# jogwheel.net
KiCad netlist of a schematic drawn in EAGLE
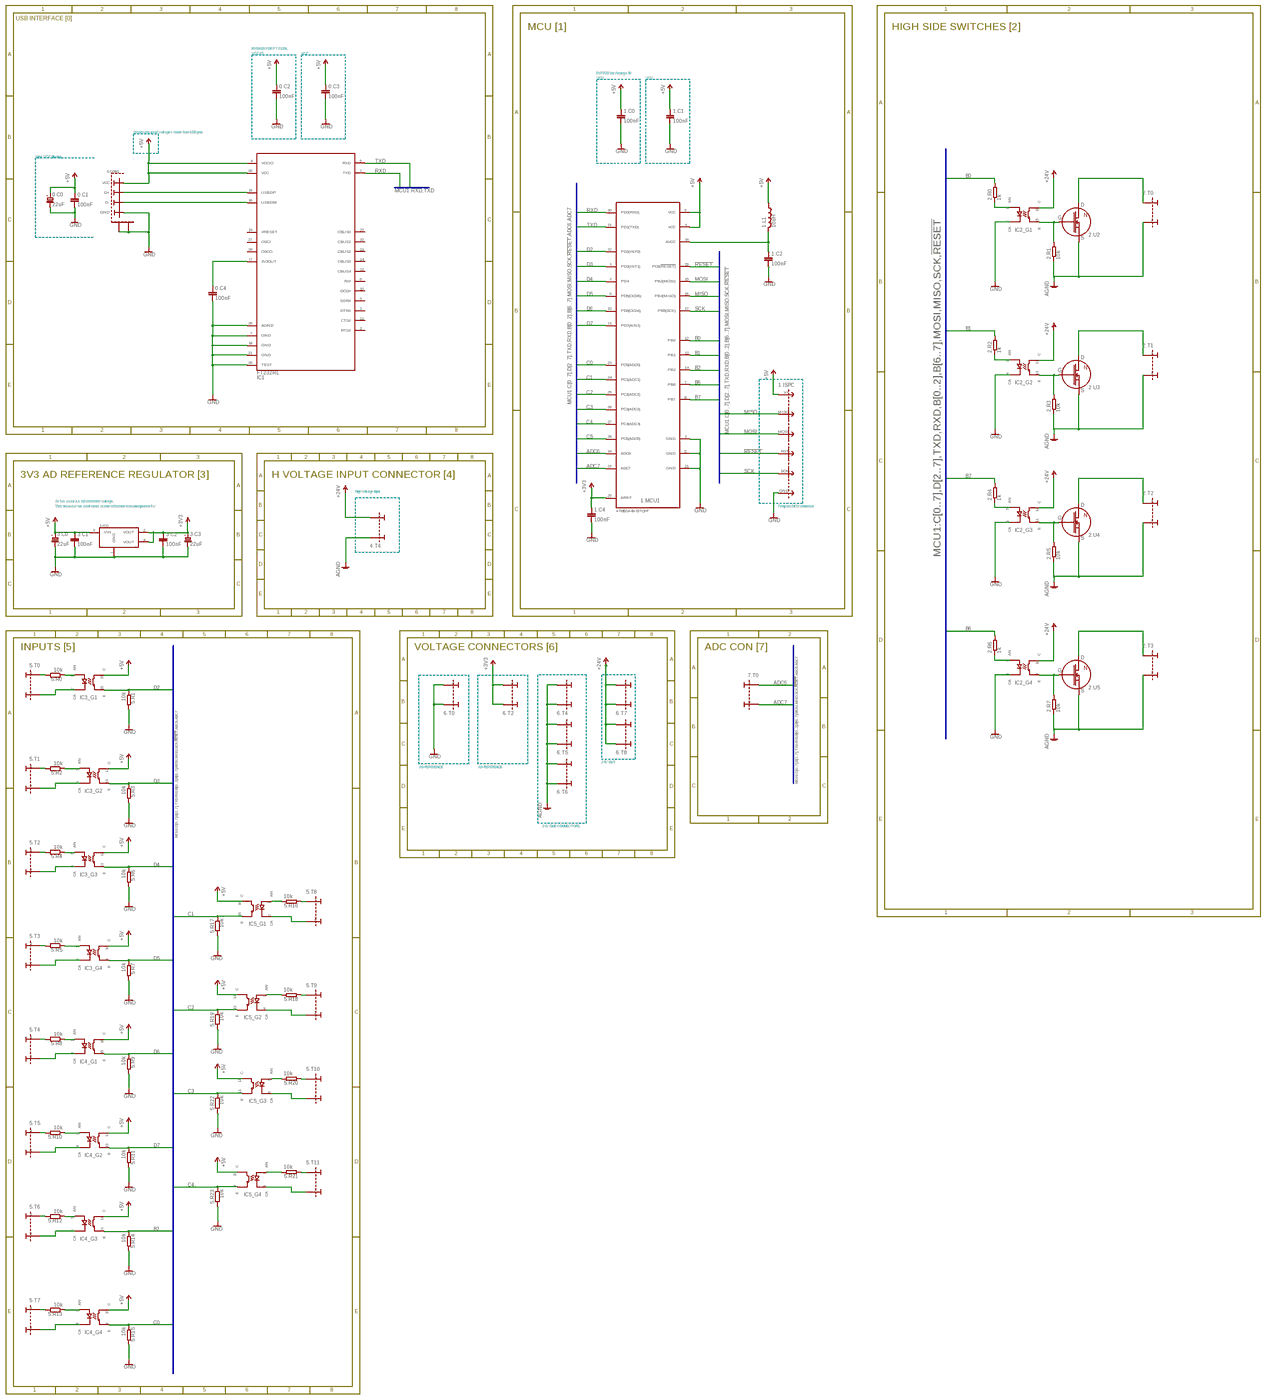
[diagram p0: schematic, sheet 1, overview]
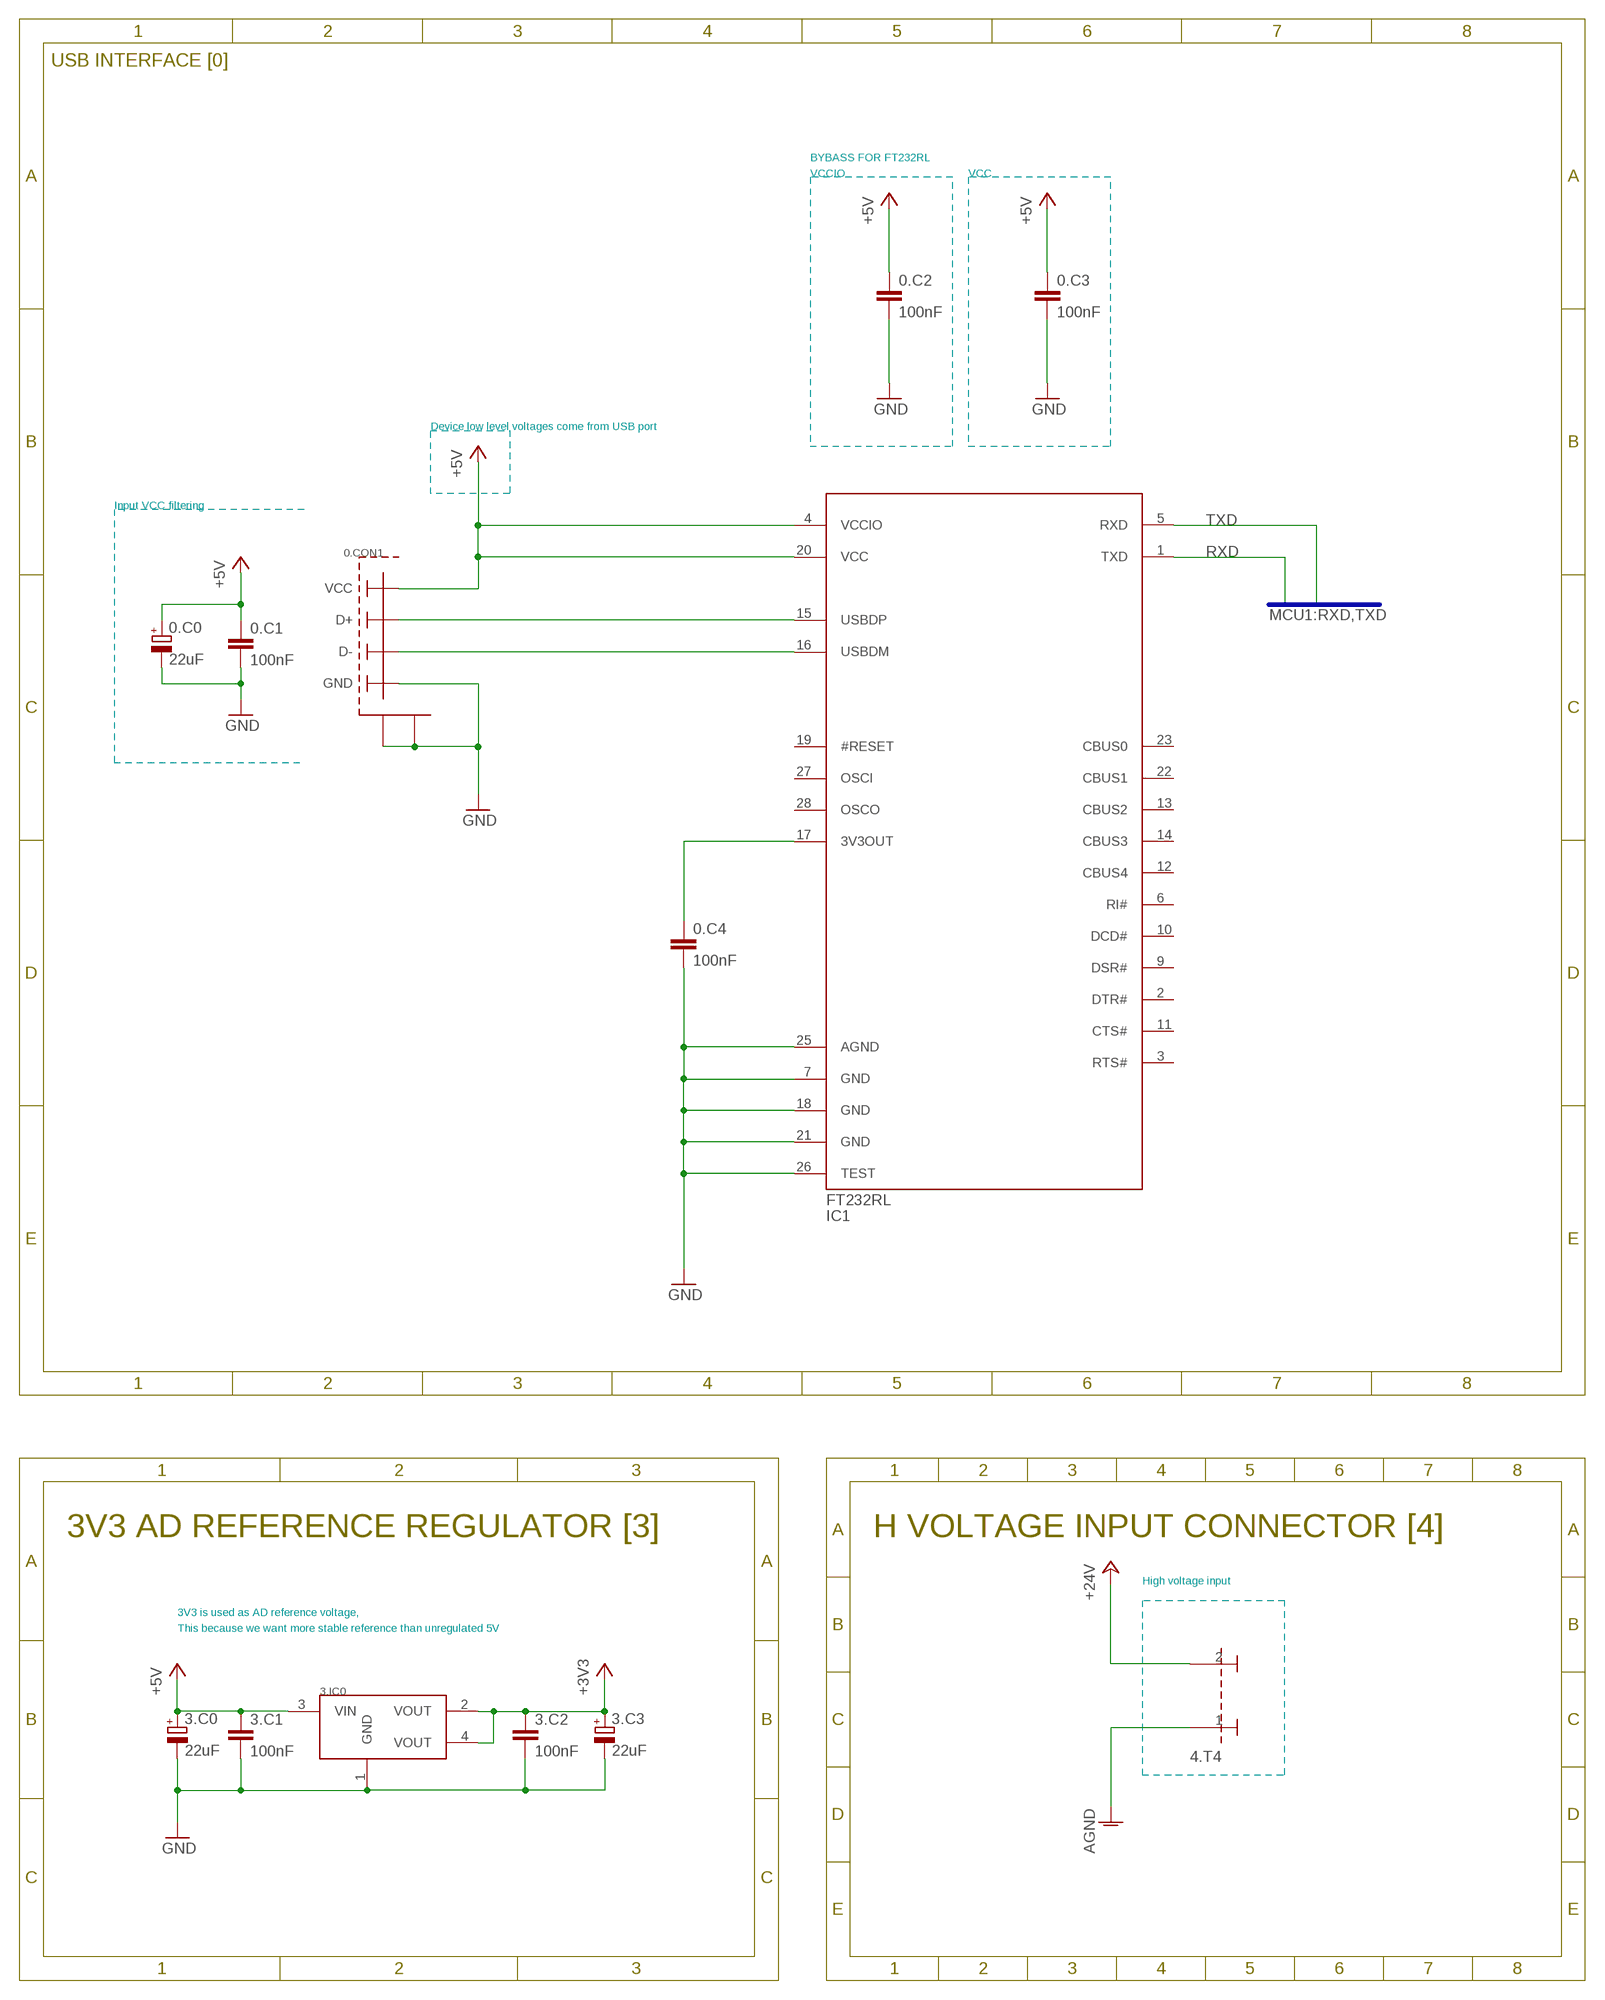
[diagram p1: schematic, sheet 1, part 1 of 4]
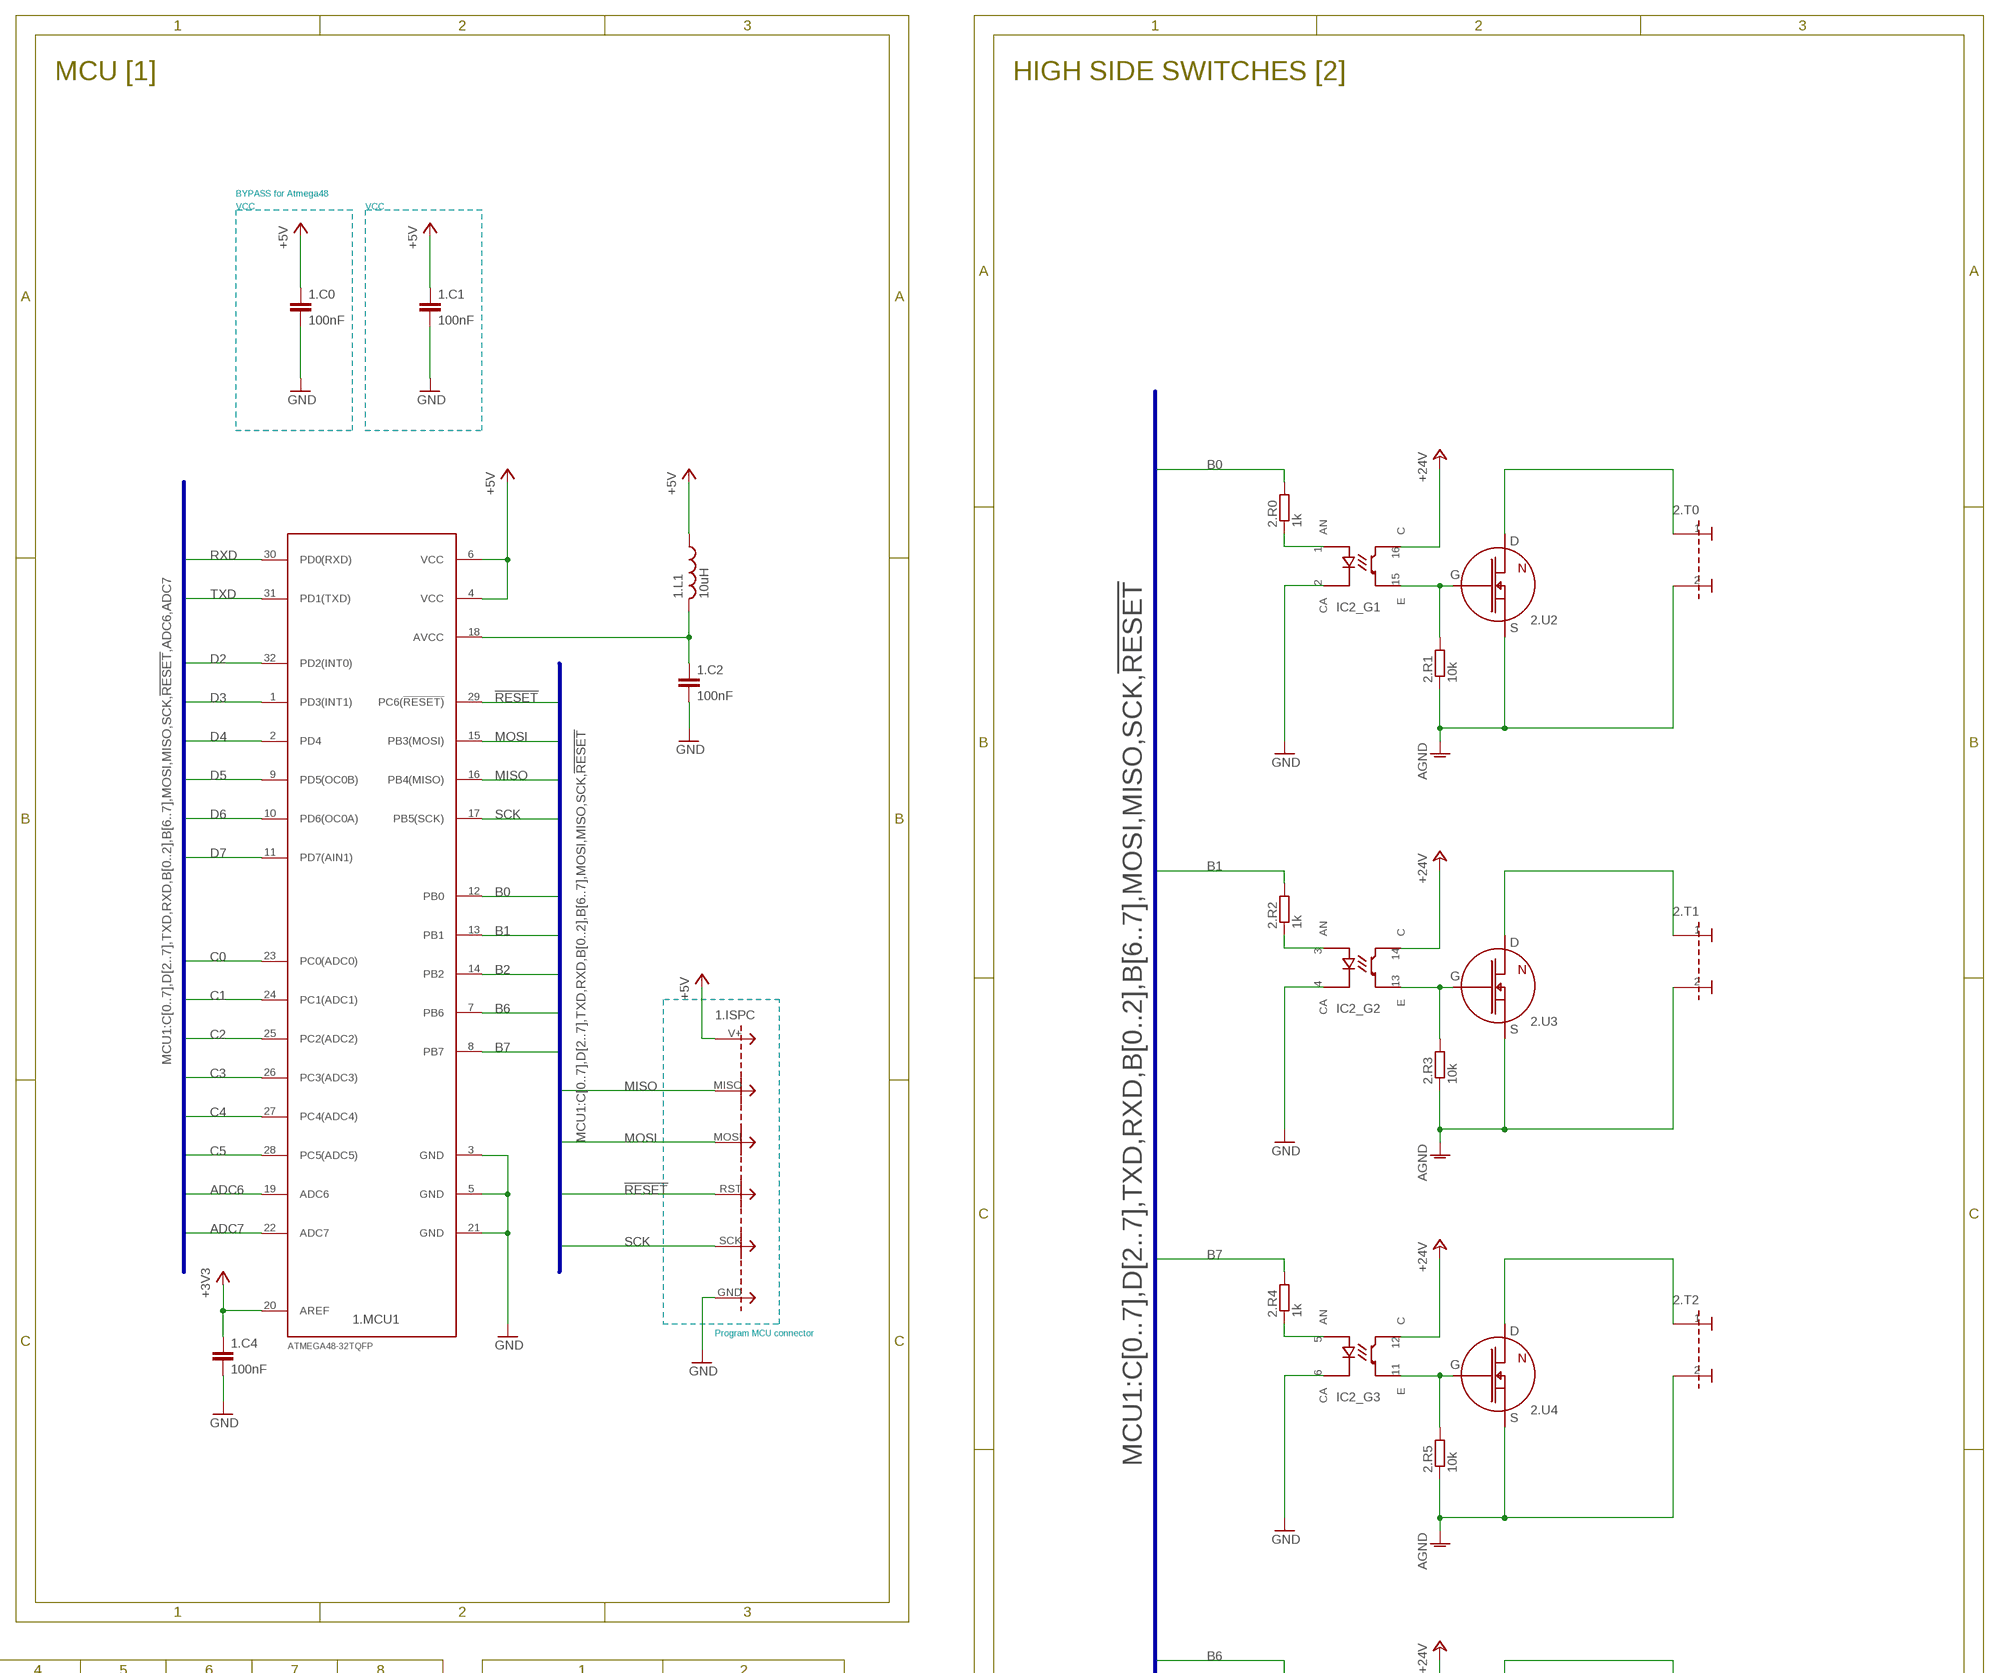
[diagram p2: schematic, sheet 1, part 2 of 4]
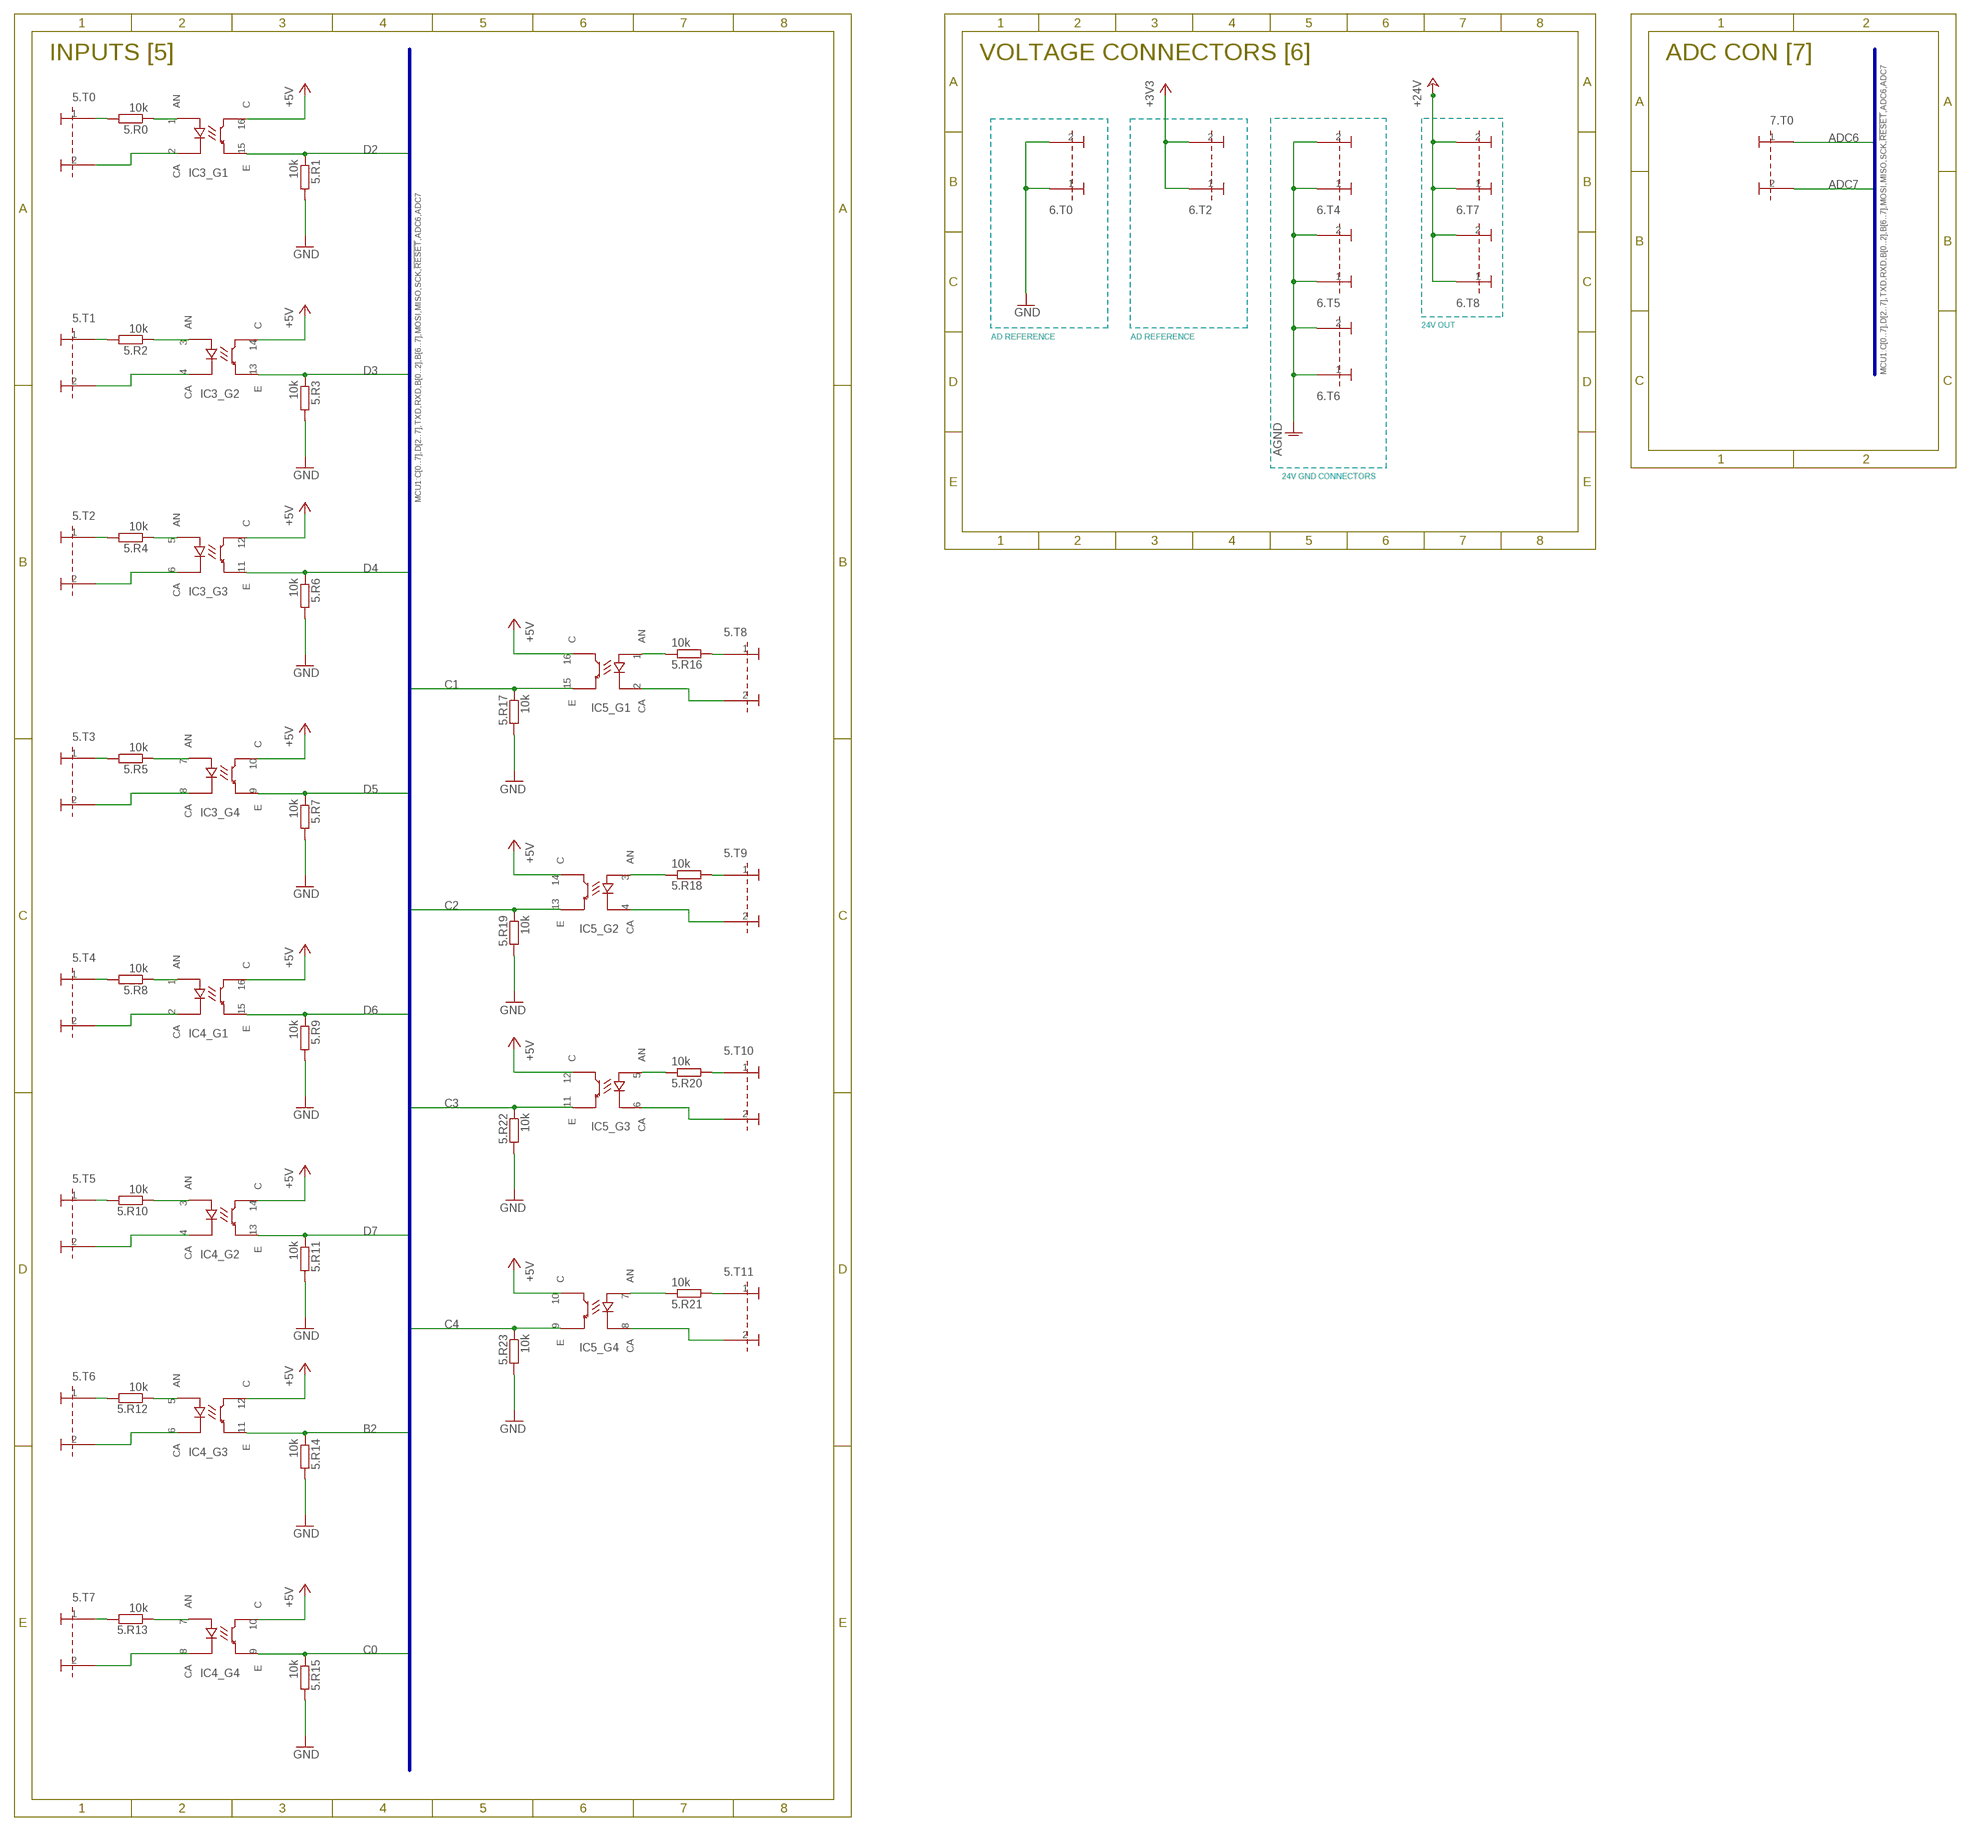
[diagram p3: schematic, sheet 1, part 3 of 4]
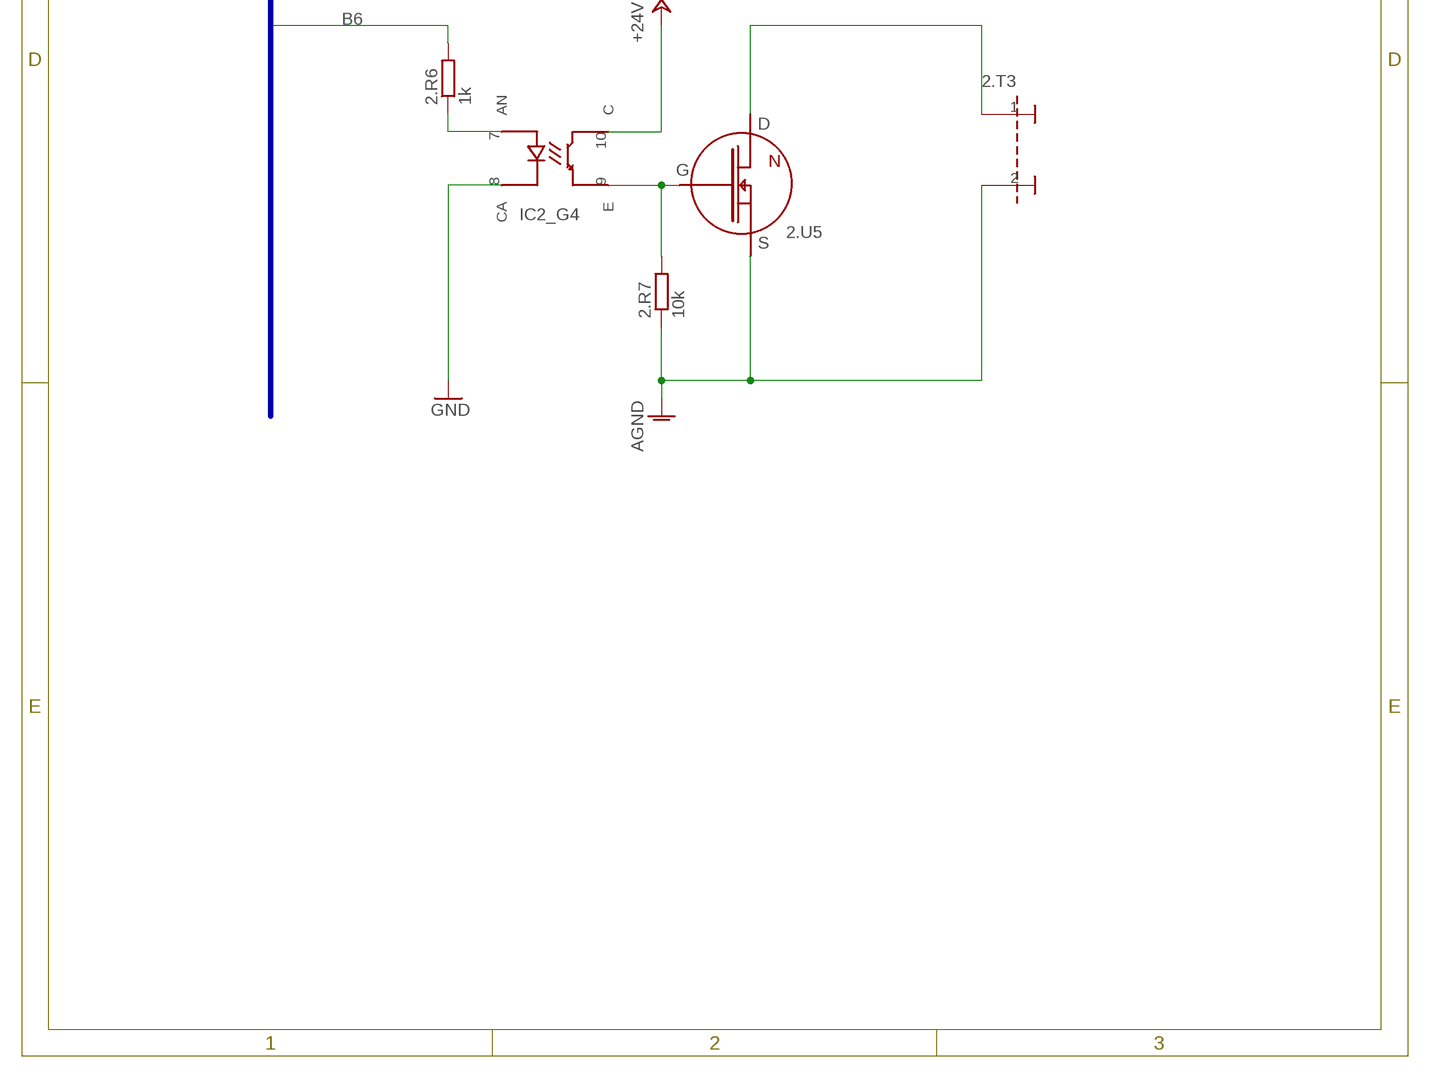
[diagram p4: schematic, sheet 1, part 4 of 4]

(export (version "E")
  (design (tool "Eeschema 10.0.6"))
  (components
    (comp (ref "0.C0")
      (value "22uF")
      (footprint "eagle-import:E1.5-5")
      (libsource (lib "eagle-import") (part "CPOL-EUE1.5-5"))
    )
    (comp (ref "0.C1")
      (value "100nF")
      (footprint "eagle-import:C0805")
      (libsource (lib "eagle-import") (part "C-EUC0805"))
    )
    (comp (ref "0.C2")
      (value "100nF")
      (footprint "eagle-import:C0805")
      (libsource (lib "eagle-import") (part "C-EUC0805"))
    )
    (comp (ref "0.C3")
      (value "100nF")
      (footprint "eagle-import:C0805")
      (libsource (lib "eagle-import") (part "C-EUC0805"))
    )
    (comp (ref "0.C4")
      (value "100nF")
      (footprint "eagle-import:C0805")
      (libsource (lib "eagle-import") (part "C-EUC0805"))
    )
    (comp (ref "0.CON1")
      (value "USB-BWUERTH-ELECTRONIC-USB-B")
      (footprint "eagle-import:USB-B-THROUGH-HOLE")
      (libsource (lib "eagle-import") (part "USB-BWUERTH-ELECTRONIC-USB-B"))
    )
    (comp (ref "1.C0")
      (value "100nF")
      (footprint "eagle-import:C0805")
      (libsource (lib "eagle-import") (part "C-EUC0805"))
    )
    (comp (ref "1.C1")
      (value "100nF")
      (footprint "eagle-import:C0805")
      (libsource (lib "eagle-import") (part "C-EUC0805"))
    )
    (comp (ref "1.C2")
      (value "100nF")
      (footprint "eagle-import:C0805")
      (libsource (lib "eagle-import") (part "C-EUC0805"))
    )
    (comp (ref "1.C4")
      (value "100nF")
      (footprint "eagle-import:C0805")
      (libsource (lib "eagle-import") (part "C-EUC0805"))
    )
    (comp (ref "1.ISPC")
      (value "CONNECTOR_6PIN2X3_ISP")
      (footprint "eagle-import:2X3_ISP")
      (libsource (lib "eagle-import") (part "CONNECTOR_6PIN2X3_ISP"))
    )
    (comp (ref "1.L1")
      (value "10uH")
      (footprint "eagle-import:C0805")
      (libsource (lib "eagle-import") (part "L_10UH_0805_LB2012T100KR"))
    )
    (comp (ref "1.MCU1")
      (value "ATMEGA48-20PU-32TQFPTQFP32")
      (footprint "eagle-import:TQFP32-08")
      (libsource (lib "eagle-import") (part "ATMEGA48-20PU-32TQFPTQFP32"))
    )
    (comp (ref "2.R0")
      (value "1k")
      (footprint "eagle-import:R0805")
      (libsource (lib "eagle-import") (part "R-EU_R0805"))
    )
    (comp (ref "2.R1")
      (value "10k")
      (footprint "eagle-import:R0805")
      (libsource (lib "eagle-import") (part "R-EU_R0805"))
    )
    (comp (ref "2.R2")
      (value "1k")
      (footprint "eagle-import:R0805")
      (libsource (lib "eagle-import") (part "R-EU_R0805"))
    )
    (comp (ref "2.R3")
      (value "10k")
      (footprint "eagle-import:R0805")
      (libsource (lib "eagle-import") (part "R-EU_R0805"))
    )
    (comp (ref "2.R4")
      (value "1k")
      (footprint "eagle-import:R0805")
      (libsource (lib "eagle-import") (part "R-EU_R0805"))
    )
    (comp (ref "2.R5")
      (value "10k")
      (footprint "eagle-import:R0805")
      (libsource (lib "eagle-import") (part "R-EU_R0805"))
    )
    (comp (ref "2.R6")
      (value "1k")
      (footprint "eagle-import:R0805")
      (libsource (lib "eagle-import") (part "R-EU_R0805"))
    )
    (comp (ref "2.R7")
      (value "10k")
      (footprint "eagle-import:R0805")
      (libsource (lib "eagle-import") (part "R-EU_R0805"))
    )
    (comp (ref "2.T0")
      (value "CONNECTOR_2PIN2W-TERMINAL-HEADER-20.155MV/2")
      (footprint "eagle-import:2WAY-TERMINAL-HEADER-20.155MV_2")
      (fields (field (name "PIN1") "DRAIN") (field (name "PIN2") "AGND"))
      (libsource (lib "eagle-import") (part "CONNECTOR_2PIN2W-TERMINAL-HEADER-20.155MV/2"))
    )
    (comp (ref "2.T1")
      (value "CONNECTOR_2PIN2W-TERMINAL-HEADER-20.155MV/2")
      (footprint "eagle-import:2WAY-TERMINAL-HEADER-20.155MV_2")
      (fields (field (name "PIN1") "DRAIN") (field (name "PIN2") "AGND"))
      (libsource (lib "eagle-import") (part "CONNECTOR_2PIN2W-TERMINAL-HEADER-20.155MV/2"))
    )
    (comp (ref "2.T2")
      (value "CONNECTOR_2PIN2W-TERMINAL-HEADER-20.155MV/2")
      (footprint "eagle-import:2WAY-TERMINAL-HEADER-20.155MV_2")
      (fields (field (name "PIN1") "DRAIN") (field (name "PIN2") "AGND"))
      (libsource (lib "eagle-import") (part "CONNECTOR_2PIN2W-TERMINAL-HEADER-20.155MV/2"))
    )
    (comp (ref "2.T3")
      (value "CONNECTOR_2PIN2W-TERMINAL-HEADER-20.155MV/2")
      (footprint "eagle-import:2WAY-TERMINAL-HEADER-20.155MV_2")
      (fields (field (name "PIN1") "DRAIN") (field (name "PIN2") "AGND"))
      (libsource (lib "eagle-import") (part "CONNECTOR_2PIN2W-TERMINAL-HEADER-20.155MV/2"))
    )
    (comp (ref "2.U2")
      (value "N_MOSFET_STD6NF10")
      (footprint "eagle-import:STD6NF10")
      (libsource (lib "eagle-import") (part "N_MOSFET_STD6NF10"))
    )
    (comp (ref "2.U3")
      (value "N_MOSFET_STD6NF10")
      (footprint "eagle-import:STD6NF10")
      (libsource (lib "eagle-import") (part "N_MOSFET_STD6NF10"))
    )
    (comp (ref "2.U4")
      (value "N_MOSFET_STD6NF10")
      (footprint "eagle-import:STD6NF10")
      (libsource (lib "eagle-import") (part "N_MOSFET_STD6NF10"))
    )
    (comp (ref "2.U5")
      (value "N_MOSFET_STD6NF10")
      (footprint "eagle-import:STD6NF10")
      (libsource (lib "eagle-import") (part "N_MOSFET_STD6NF10"))
    )
    (comp (ref "3.C0")
      (value "22uF")
      (footprint "eagle-import:E1.5-5")
      (libsource (lib "eagle-import") (part "CPOL-EUE1.5-5"))
    )
    (comp (ref "3.C1")
      (value "100nF")
      (footprint "eagle-import:C0805")
      (libsource (lib "eagle-import") (part "C-EUC0805"))
    )
    (comp (ref "3.C2")
      (value "100nF")
      (footprint "eagle-import:C0805")
      (libsource (lib "eagle-import") (part "C-EUC0805"))
    )
    (comp (ref "3.C3")
      (value "22uF")
      (footprint "eagle-import:E1.5-5")
      (libsource (lib "eagle-import") (part "CPOL-EUE1.5-5"))
    )
    (comp (ref "3.IC0")
      (value "REGULATOR_AP1117E33G-13")
      (footprint "eagle-import:SOT223")
      (libsource (lib "eagle-import") (part "REGULATOR_AP1117E33G-13"))
    )
    (comp (ref "4.T4")
      (value "CONNECTOR_2PIN2W-TERMINAL-HEADER-20.155MV/2")
      (footprint "eagle-import:2WAY-TERMINAL-HEADER-20.155MV_2")
      (fields (field (name "PIN1") "AGND") (field (name "PIN2") "24VIN"))
      (libsource (lib "eagle-import") (part "CONNECTOR_2PIN2W-TERMINAL-HEADER-20.155MV/2"))
    )
    (comp (ref "5.R0")
      (value "10k")
      (footprint "eagle-import:R0805")
      (libsource (lib "eagle-import") (part "R-EU_R0805"))
    )
    (comp (ref "5.R1")
      (value "10k")
      (footprint "eagle-import:R0805")
      (libsource (lib "eagle-import") (part "R-EU_R0805"))
    )
    (comp (ref "5.R2")
      (value "10k")
      (footprint "eagle-import:R0805")
      (libsource (lib "eagle-import") (part "R-EU_R0805"))
    )
    (comp (ref "5.R3")
      (value "10k")
      (footprint "eagle-import:R0805")
      (libsource (lib "eagle-import") (part "R-EU_R0805"))
    )
    (comp (ref "5.R4")
      (value "10k")
      (footprint "eagle-import:R0805")
      (libsource (lib "eagle-import") (part "R-EU_R0805"))
    )
    (comp (ref "5.R5")
      (value "10k")
      (footprint "eagle-import:R0805")
      (libsource (lib "eagle-import") (part "R-EU_R0805"))
    )
    (comp (ref "5.R6")
      (value "10k")
      (footprint "eagle-import:R0805")
      (libsource (lib "eagle-import") (part "R-EU_R0805"))
    )
    (comp (ref "5.R7")
      (value "10k")
      (footprint "eagle-import:R0805")
      (libsource (lib "eagle-import") (part "R-EU_R0805"))
    )
    (comp (ref "5.R8")
      (value "10k")
      (footprint "eagle-import:R0805")
      (libsource (lib "eagle-import") (part "R-EU_R0805"))
    )
    (comp (ref "5.R9")
      (value "10k")
      (footprint "eagle-import:R0805")
      (libsource (lib "eagle-import") (part "R-EU_R0805"))
    )
    (comp (ref "5.R10")
      (value "10k")
      (footprint "eagle-import:R0805")
      (libsource (lib "eagle-import") (part "R-EU_R0805"))
    )
    (comp (ref "5.R11")
      (value "10k")
      (footprint "eagle-import:R0805")
      (libsource (lib "eagle-import") (part "R-EU_R0805"))
    )
    (comp (ref "5.R12")
      (value "10k")
      (footprint "eagle-import:R0805")
      (libsource (lib "eagle-import") (part "R-EU_R0805"))
    )
    (comp (ref "5.R13")
      (value "10k")
      (footprint "eagle-import:R0805")
      (libsource (lib "eagle-import") (part "R-EU_R0805"))
    )
    (comp (ref "5.R14")
      (value "10k")
      (footprint "eagle-import:R0805")
      (libsource (lib "eagle-import") (part "R-EU_R0805"))
    )
    (comp (ref "5.R15")
      (value "10k")
      (footprint "eagle-import:R0805")
      (libsource (lib "eagle-import") (part "R-EU_R0805"))
    )
    (comp (ref "5.R16")
      (value "10k")
      (footprint "eagle-import:R0805")
      (libsource (lib "eagle-import") (part "R-EU_R0805"))
    )
    (comp (ref "5.R17")
      (value "10k")
      (footprint "eagle-import:R0805")
      (libsource (lib "eagle-import") (part "R-EU_R0805"))
    )
    (comp (ref "5.R18")
      (value "10k")
      (footprint "eagle-import:R0805")
      (libsource (lib "eagle-import") (part "R-EU_R0805"))
    )
    (comp (ref "5.R19")
      (value "10k")
      (footprint "eagle-import:R0805")
      (libsource (lib "eagle-import") (part "R-EU_R0805"))
    )
    (comp (ref "5.R20")
      (value "10k")
      (footprint "eagle-import:R0805")
      (libsource (lib "eagle-import") (part "R-EU_R0805"))
    )
    (comp (ref "5.R21")
      (value "10k")
      (footprint "eagle-import:R0805")
      (libsource (lib "eagle-import") (part "R-EU_R0805"))
    )
    (comp (ref "5.R22")
      (value "10k")
      (footprint "eagle-import:R0805")
      (libsource (lib "eagle-import") (part "R-EU_R0805"))
    )
    (comp (ref "5.R23")
      (value "10k")
      (footprint "eagle-import:R0805")
      (libsource (lib "eagle-import") (part "R-EU_R0805"))
    )
    (comp (ref "5.T0")
      (value "CONNECTOR_2PIN2W-TERMINAL-HEADER-20.155MV/2")
      (footprint "eagle-import:2WAY-TERMINAL-HEADER-20.155MV_2")
      (fields (field (name "PIN1") "V+") (field (name "PIN2") "V-"))
      (libsource (lib "eagle-import") (part "CONNECTOR_2PIN2W-TERMINAL-HEADER-20.155MV/2"))
    )
    (comp (ref "5.T1")
      (value "CONNECTOR_2PIN2W-TERMINAL-HEADER-20.155MV/2")
      (footprint "eagle-import:2WAY-TERMINAL-HEADER-20.155MV_2")
      (fields (field (name "PIN1") "V+") (field (name "PIN2") "V-"))
      (libsource (lib "eagle-import") (part "CONNECTOR_2PIN2W-TERMINAL-HEADER-20.155MV/2"))
    )
    (comp (ref "5.T2")
      (value "CONNECTOR_2PIN2W-TERMINAL-HEADER-20.155MV/2")
      (footprint "eagle-import:2WAY-TERMINAL-HEADER-20.155MV_2")
      (fields (field (name "PIN1") "V+") (field (name "PIN2") "V-"))
      (libsource (lib "eagle-import") (part "CONNECTOR_2PIN2W-TERMINAL-HEADER-20.155MV/2"))
    )
    (comp (ref "5.T3")
      (value "CONNECTOR_2PIN2W-TERMINAL-HEADER-20.155MV/2")
      (footprint "eagle-import:2WAY-TERMINAL-HEADER-20.155MV_2")
      (fields (field (name "PIN1") "V+") (field (name "PIN2") "V-"))
      (libsource (lib "eagle-import") (part "CONNECTOR_2PIN2W-TERMINAL-HEADER-20.155MV/2"))
    )
    (comp (ref "5.T4")
      (value "CONNECTOR_2PIN2W-TERMINAL-HEADER-20.155MV/2")
      (footprint "eagle-import:2WAY-TERMINAL-HEADER-20.155MV_2")
      (fields (field (name "PIN1") "V+") (field (name "PIN2") "V-"))
      (libsource (lib "eagle-import") (part "CONNECTOR_2PIN2W-TERMINAL-HEADER-20.155MV/2"))
    )
    (comp (ref "5.T5")
      (value "CONNECTOR_2PIN2W-TERMINAL-HEADER-20.155MV/2")
      (footprint "eagle-import:2WAY-TERMINAL-HEADER-20.155MV_2")
      (fields (field (name "PIN1") "V+") (field (name "PIN2") "V-"))
      (libsource (lib "eagle-import") (part "CONNECTOR_2PIN2W-TERMINAL-HEADER-20.155MV/2"))
    )
    (comp (ref "5.T6")
      (value "CONNECTOR_2PIN2W-TERMINAL-HEADER-20.155MV/2")
      (footprint "eagle-import:2WAY-TERMINAL-HEADER-20.155MV_2")
      (fields (field (name "PIN1") "V+") (field (name "PIN2") "V-"))
      (libsource (lib "eagle-import") (part "CONNECTOR_2PIN2W-TERMINAL-HEADER-20.155MV/2"))
    )
    (comp (ref "5.T7")
      (value "CONNECTOR_2PIN2W-TERMINAL-HEADER-20.155MV/2")
      (footprint "eagle-import:2WAY-TERMINAL-HEADER-20.155MV_2")
      (fields (field (name "PIN1") "V+") (field (name "PIN2") "V-"))
      (libsource (lib "eagle-import") (part "CONNECTOR_2PIN2W-TERMINAL-HEADER-20.155MV/2"))
    )
    (comp (ref "5.T8")
      (value "CONNECTOR_2PIN2W-TERMINAL-HEADER-20.155MV/2")
      (footprint "eagle-import:2WAY-TERMINAL-HEADER-20.155MV_2")
      (fields (field (name "PIN1") "V+") (field (name "PIN2") "V-"))
      (libsource (lib "eagle-import") (part "CONNECTOR_2PIN2W-TERMINAL-HEADER-20.155MV/2"))
    )
    (comp (ref "5.T9")
      (value "CONNECTOR_2PIN2W-TERMINAL-HEADER-20.155MV/2")
      (footprint "eagle-import:2WAY-TERMINAL-HEADER-20.155MV_2")
      (fields (field (name "PIN1") "V+") (field (name "PIN2") "V-"))
      (libsource (lib "eagle-import") (part "CONNECTOR_2PIN2W-TERMINAL-HEADER-20.155MV/2"))
    )
    (comp (ref "5.T10")
      (value "CONNECTOR_2PIN2W-TERMINAL-HEADER-20.155MV/2")
      (footprint "eagle-import:2WAY-TERMINAL-HEADER-20.155MV_2")
      (fields (field (name "PIN1") "V+") (field (name "PIN2") "V-"))
      (libsource (lib "eagle-import") (part "CONNECTOR_2PIN2W-TERMINAL-HEADER-20.155MV/2"))
    )
    (comp (ref "5.T11")
      (value "CONNECTOR_2PIN2W-TERMINAL-HEADER-20.155MV/2")
      (footprint "eagle-import:2WAY-TERMINAL-HEADER-20.155MV_2")
      (fields (field (name "PIN1") "V+") (field (name "PIN2") "V-"))
      (libsource (lib "eagle-import") (part "CONNECTOR_2PIN2W-TERMINAL-HEADER-20.155MV/2"))
    )
    (comp (ref "6.T0")
      (value "CONNECTOR_2PIN2W-TERMINAL-HEADER-20.155MV/2")
      (footprint "eagle-import:2WAY-TERMINAL-HEADER-20.155MV_2")
      (fields (field (name "PIN1") "GND") (field (name "PIN2") "GND"))
      (libsource (lib "eagle-import") (part "CONNECTOR_2PIN2W-TERMINAL-HEADER-20.155MV/2"))
    )
    (comp (ref "6.T2")
      (value "CONNECTOR_2PIN2W-TERMINAL-HEADER-20.155MV/2")
      (footprint "eagle-import:2WAY-TERMINAL-HEADER-20.155MV_2")
      (fields (field (name "PIN1") "AREF") (field (name "PIN2") "AREF"))
      (libsource (lib "eagle-import") (part "CONNECTOR_2PIN2W-TERMINAL-HEADER-20.155MV/2"))
    )
    (comp (ref "6.T4")
      (value "CONNECTOR_2PIN2W-TERMINAL-HEADER-20.155MV/2")
      (footprint "eagle-import:2WAY-TERMINAL-HEADER-20.155MV_2")
      (fields (field (name "PIN1") "AGND") (field (name "PIN2") "AGND"))
      (libsource (lib "eagle-import") (part "CONNECTOR_2PIN2W-TERMINAL-HEADER-20.155MV/2"))
    )
    (comp (ref "6.T5")
      (value "CONNECTOR_2PIN2W-TERMINAL-HEADER-20.155MV/2")
      (footprint "eagle-import:2WAY-TERMINAL-HEADER-20.155MV_2")
      (fields (field (name "PIN1") "AGND") (field (name "PIN2") "AGND"))
      (libsource (lib "eagle-import") (part "CONNECTOR_2PIN2W-TERMINAL-HEADER-20.155MV/2"))
    )
    (comp (ref "6.T6")
      (value "CONNECTOR_2PIN2W-TERMINAL-HEADER-20.155MV/2")
      (footprint "eagle-import:2WAY-TERMINAL-HEADER-20.155MV_2")
      (fields (field (name "PIN1") "AGND") (field (name "PIN2") "AGND"))
      (libsource (lib "eagle-import") (part "CONNECTOR_2PIN2W-TERMINAL-HEADER-20.155MV/2"))
    )
    (comp (ref "6.T7")
      (value "CONNECTOR_2PIN2W-TERMINAL-HEADER-20.155MV/2")
      (footprint "eagle-import:2WAY-TERMINAL-HEADER-20.155MV_2")
      (fields (field (name "PIN1") "24V") (field (name "PIN2") "24V"))
      (libsource (lib "eagle-import") (part "CONNECTOR_2PIN2W-TERMINAL-HEADER-20.155MV/2"))
    )
    (comp (ref "6.T8")
      (value "CONNECTOR_2PIN2W-TERMINAL-HEADER-20.155MV/2")
      (footprint "eagle-import:2WAY-TERMINAL-HEADER-20.155MV_2")
      (fields (field (name "PIN1") "24V") (field (name "PIN2") "24V"))
      (libsource (lib "eagle-import") (part "CONNECTOR_2PIN2W-TERMINAL-HEADER-20.155MV/2"))
    )
    (comp (ref "7.T0")
      (value "CONNECTOR_2PIN2W-TERMINAL-HEADER-20.155MV/2")
      (footprint "eagle-import:2WAY-TERMINAL-HEADER-20.155MV_2")
      (fields (field (name "PIN1") "ADC0") (field (name "PIN2") "ADC1"))
      (libsource (lib "eagle-import") (part "CONNECTOR_2PIN2W-TERMINAL-HEADER-20.155MV/2"))
    )
    (comp (ref "IC1")
      (value "FT232RL")
      (footprint "eagle-import:SSOP28")
      (libsource (lib "eagle-import") (part "FT232RL"))
    )
    (comp (ref "IC2")
      (value "OPTO_4_CHANNELS")
      (footprint "eagle-import:ACPL-845-O300")
      (libsource (lib "eagle-import") (part "OPTO_4_CHANNELS"))
    )
    (comp (ref "IC3")
      (value "OPTO_4_CHANNELS")
      (footprint "eagle-import:ACPL-845-O300")
      (libsource (lib "eagle-import") (part "OPTO_4_CHANNELS"))
    )
    (comp (ref "IC4")
      (value "OPTO_4_CHANNELS")
      (footprint "eagle-import:ACPL-845-O300")
      (libsource (lib "eagle-import") (part "OPTO_4_CHANNELS"))
    )
    (comp (ref "IC5")
      (value "OPTO_4_CHANNELS")
      (footprint "eagle-import:ACPL-845-O300")
      (libsource (lib "eagle-import") (part "OPTO_4_CHANNELS"))
    )
  )
  (nets
    (net (code "2") (name "+3V3") (class "Default")
      (node (ref "1.C4") (pin "1") (pinfunction "1_1") (pintype "passive"))
      (node (ref "1.MCU1") (pin "20") (pinfunction "AREF_20") (pintype "bidirectional"))
      (node (ref "3.C2") (pin "1") (pinfunction "1_1") (pintype "passive"))
      (node (ref "3.C3") (pin "+") (pinfunction "+_+") (pintype "passive"))
      (node (ref "3.IC0") (pin "2") (pinfunction "VOUT_2") (pintype "bidirectional"))
      (node (ref "3.IC0") (pin "4") (pinfunction "VOUT_4") (pintype "bidirectional"))
      (node (ref "6.T2") (pin "1") (pinfunction "P$1_1") (pintype "bidirectional"))
      (node (ref "6.T2") (pin "2") (pinfunction "P$2_2") (pintype "bidirectional"))
    )
    (net (code "3") (name "+5V") (class "Default")
      (node (ref "0.C0") (pin "+") (pinfunction "+_+") (pintype "passive"))
      (node (ref "0.C1") (pin "1") (pinfunction "1_1") (pintype "passive"))
      (node (ref "0.C2") (pin "1") (pinfunction "1_1") (pintype "passive"))
      (node (ref "0.C3") (pin "1") (pinfunction "1_1") (pintype "passive"))
      (node (ref "0.CON1") (pin "VCC") (pinfunction "VCC_VCC") (pintype "bidirectional"))
      (node (ref "1.C0") (pin "1") (pinfunction "1_1") (pintype "passive"))
      (node (ref "1.C1") (pin "1") (pinfunction "1_1") (pintype "passive"))
      (node (ref "1.ISPC") (pin "V+") (pinfunction "P$1_V+") (pintype "bidirectional"))
      (node (ref "1.L1") (pin "1") (pinfunction "1_1") (pintype "passive"))
      (node (ref "1.MCU1") (pin "4") (pinfunction "VCC_4") (pintype "bidirectional"))
      (node (ref "1.MCU1") (pin "6") (pinfunction "VCC_6") (pintype "bidirectional"))
      (node (ref "3.C0") (pin "+") (pinfunction "+_+") (pintype "passive"))
      (node (ref "3.C1") (pin "1") (pinfunction "1_1") (pintype "passive"))
      (node (ref "3.IC0") (pin "3") (pinfunction "VIN_3") (pintype "bidirectional"))
      (node (ref "IC1") (pin "20") (pinfunction "VCC_20") (pintype "bidirectional"))
      (node (ref "IC1") (pin "4") (pinfunction "VCCIO_4") (pintype "bidirectional"))
      (node (ref "IC3") (pin "10") (pinfunction "C_10") (pintype "bidirectional"))
      (node (ref "IC3") (pin "12") (pinfunction "C_12") (pintype "bidirectional"))
      (node (ref "IC3") (pin "14") (pinfunction "C_14") (pintype "bidirectional"))
      (node (ref "IC3") (pin "16") (pinfunction "C_16") (pintype "bidirectional"))
      (node (ref "IC4") (pin "10") (pinfunction "C_10") (pintype "bidirectional"))
      (node (ref "IC4") (pin "12") (pinfunction "C_12") (pintype "bidirectional"))
      (node (ref "IC4") (pin "14") (pinfunction "C_14") (pintype "bidirectional"))
      (node (ref "IC4") (pin "16") (pinfunction "C_16") (pintype "bidirectional"))
      (node (ref "IC5") (pin "10") (pinfunction "C_10") (pintype "bidirectional"))
      (node (ref "IC5") (pin "12") (pinfunction "C_12") (pintype "bidirectional"))
      (node (ref "IC5") (pin "14") (pinfunction "C_14") (pintype "bidirectional"))
      (node (ref "IC5") (pin "16") (pinfunction "C_16") (pintype "bidirectional"))
    )
    (net (code "4") (name "+24V") (class "Default")
      (node (ref "4.T4") (pin "2") (pinfunction "P$2_2") (pintype "bidirectional"))
      (node (ref "6.T7") (pin "1") (pinfunction "P$1_1") (pintype "bidirectional"))
      (node (ref "6.T7") (pin "2") (pinfunction "P$2_2") (pintype "bidirectional"))
      (node (ref "6.T8") (pin "1") (pinfunction "P$1_1") (pintype "bidirectional"))
      (node (ref "6.T8") (pin "2") (pinfunction "P$2_2") (pintype "bidirectional"))
      (node (ref "IC2") (pin "10") (pinfunction "C_10") (pintype "bidirectional"))
      (node (ref "IC2") (pin "12") (pinfunction "C_12") (pintype "bidirectional"))
      (node (ref "IC2") (pin "14") (pinfunction "C_14") (pintype "bidirectional"))
      (node (ref "IC2") (pin "16") (pinfunction "C_16") (pintype "bidirectional"))
    )
    (net (code "5") (name "/ADC6") (class "Default")
      (node (ref "1.MCU1") (pin "19") (pinfunction "ADC6_19") (pintype "bidirectional"))
      (node (ref "7.T0") (pin "1") (pinfunction "P$1_1") (pintype "bidirectional"))
    )
    (net (code "6") (name "/ADC7") (class "Default")
      (node (ref "1.MCU1") (pin "22") (pinfunction "ADC7_22") (pintype "bidirectional"))
      (node (ref "7.T0") (pin "2") (pinfunction "P$2_2") (pintype "bidirectional"))
    )
    (net (code "7") (name "/B0") (class "Default")
      (node (ref "1.MCU1") (pin "12") (pinfunction "PB0_12") (pintype "bidirectional"))
      (node (ref "2.R0") (pin "2") (pinfunction "2_2") (pintype "passive"))
    )
    (net (code "8") (name "/B1") (class "Default")
      (node (ref "1.MCU1") (pin "13") (pinfunction "PB1_13") (pintype "bidirectional"))
      (node (ref "2.R2") (pin "2") (pinfunction "2_2") (pintype "passive"))
    )
    (net (code "9") (name "/B2") (class "Default")
      (node (ref "1.MCU1") (pin "14") (pinfunction "PB2_14") (pintype "bidirectional"))
      (node (ref "5.R14") (pin "1") (pinfunction "1_1") (pintype "passive"))
      (node (ref "IC4") (pin "11") (pinfunction "E_11") (pintype "bidirectional"))
    )
    (net (code "10") (name "/B6") (class "Default")
      (node (ref "1.MCU1") (pin "7") (pinfunction "PB6_7") (pintype "bidirectional"))
      (node (ref "2.R6") (pin "2") (pinfunction "2_2") (pintype "passive"))
    )
    (net (code "11") (name "/B7") (class "Default")
      (node (ref "1.MCU1") (pin "8") (pinfunction "PB7_8") (pintype "bidirectional"))
      (node (ref "2.R4") (pin "2") (pinfunction "2_2") (pintype "passive"))
    )
    (net (code "12") (name "/C0") (class "Default")
      (node (ref "1.MCU1") (pin "23") (pinfunction "PC0(ADC0)_23") (pintype "bidirectional"))
      (node (ref "5.R15") (pin "1") (pinfunction "1_1") (pintype "passive"))
      (node (ref "IC4") (pin "9") (pinfunction "E_9") (pintype "bidirectional"))
    )
    (net (code "13") (name "/C1") (class "Default")
      (node (ref "1.MCU1") (pin "24") (pinfunction "PC1(ADC1)_24") (pintype "bidirectional"))
      (node (ref "5.R17") (pin "1") (pinfunction "1_1") (pintype "passive"))
      (node (ref "IC5") (pin "15") (pinfunction "E_15") (pintype "bidirectional"))
    )
    (net (code "14") (name "/C2") (class "Default")
      (node (ref "1.MCU1") (pin "25") (pinfunction "PC2(ADC2)_25") (pintype "bidirectional"))
      (node (ref "5.R19") (pin "1") (pinfunction "1_1") (pintype "passive"))
      (node (ref "IC5") (pin "13") (pinfunction "E_13") (pintype "bidirectional"))
    )
    (net (code "15") (name "/C3") (class "Default")
      (node (ref "1.MCU1") (pin "26") (pinfunction "PC3(ADC3)_26") (pintype "bidirectional"))
      (node (ref "5.R22") (pin "1") (pinfunction "1_1") (pintype "passive"))
      (node (ref "IC5") (pin "11") (pinfunction "E_11") (pintype "bidirectional"))
    )
    (net (code "16") (name "/C4") (class "Default")
      (node (ref "1.MCU1") (pin "27") (pinfunction "PC4(ADC4)_27") (pintype "bidirectional"))
      (node (ref "5.R23") (pin "1") (pinfunction "1_1") (pintype "passive"))
      (node (ref "IC5") (pin "9") (pinfunction "E_9") (pintype "bidirectional"))
    )
    (net (code "17") (name "/C5") (class "Default")
      (node (ref "1.MCU1") (pin "28") (pinfunction "PC5(ADC5)_28") (pintype "bidirectional"))
    )
    (net (code "18") (name "/D2") (class "Default")
      (node (ref "1.MCU1") (pin "32") (pinfunction "PD2(INT0)_32") (pintype "bidirectional"))
      (node (ref "5.R1") (pin "1") (pinfunction "1_1") (pintype "passive"))
      (node (ref "IC3") (pin "15") (pinfunction "E_15") (pintype "bidirectional"))
    )
    (net (code "19") (name "/D3") (class "Default")
      (node (ref "1.MCU1") (pin "1") (pinfunction "PD3(INT1)_1") (pintype "bidirectional"))
      (node (ref "5.R3") (pin "1") (pinfunction "1_1") (pintype "passive"))
      (node (ref "IC3") (pin "13") (pinfunction "E_13") (pintype "bidirectional"))
    )
    (net (code "20") (name "/D4") (class "Default")
      (node (ref "1.MCU1") (pin "2") (pinfunction "PD4_2") (pintype "bidirectional"))
      (node (ref "5.R6") (pin "1") (pinfunction "1_1") (pintype "passive"))
      (node (ref "IC3") (pin "11") (pinfunction "E_11") (pintype "bidirectional"))
    )
    (net (code "21") (name "/D5") (class "Default")
      (node (ref "1.MCU1") (pin "9") (pinfunction "PD5(OC0B)_9") (pintype "bidirectional"))
      (node (ref "5.R7") (pin "1") (pinfunction "1_1") (pintype "passive"))
      (node (ref "IC3") (pin "9") (pinfunction "E_9") (pintype "bidirectional"))
    )
    (net (code "22") (name "/D6") (class "Default")
      (node (ref "1.MCU1") (pin "10") (pinfunction "PD6(OC0A)_10") (pintype "bidirectional"))
      (node (ref "5.R9") (pin "1") (pinfunction "1_1") (pintype "passive"))
      (node (ref "IC4") (pin "15") (pinfunction "E_15") (pintype "bidirectional"))
    )
    (net (code "23") (name "/D7") (class "Default")
      (node (ref "1.MCU1") (pin "11") (pinfunction "PD7(AIN1)_11") (pintype "bidirectional"))
      (node (ref "5.R11") (pin "1") (pinfunction "1_1") (pintype "passive"))
      (node (ref "IC4") (pin "13") (pinfunction "E_13") (pintype "bidirectional"))
    )
    (net (code "24") (name "/MISO") (class "Default")
      (node (ref "1.ISPC") (pin "MISO") (pinfunction "P$2_MISO") (pintype "bidirectional"))
      (node (ref "1.MCU1") (pin "16") (pinfunction "PB4(MISO)_16") (pintype "bidirectional"))
    )
    (net (code "25") (name "/MOSI") (class "Default")
      (node (ref "1.ISPC") (pin "MOSI") (pinfunction "P$3_MOSI") (pintype "bidirectional"))
      (node (ref "1.MCU1") (pin "15") (pinfunction "PB3(MOSI)_15") (pintype "bidirectional"))
    )
    (net (code "26") (name "/RXD") (class "Default")
      (node (ref "1.MCU1") (pin "30") (pinfunction "PD0(RXD)_30") (pintype "bidirectional"))
      (node (ref "IC1") (pin "1") (pinfunction "TXD_1") (pintype "bidirectional"))
    )
    (net (code "27") (name "/SCK") (class "Default")
      (node (ref "1.ISPC") (pin "SCK") (pinfunction "P$5_SCK") (pintype "bidirectional"))
      (node (ref "1.MCU1") (pin "17") (pinfunction "PB5(SCK)_17") (pintype "bidirectional"))
    )
    (net (code "28") (name "/TXD") (class "Default")
      (node (ref "1.MCU1") (pin "31") (pinfunction "PD1(TXD)_31") (pintype "bidirectional"))
      (node (ref "IC1") (pin "5") (pinfunction "RXD_5") (pintype "bidirectional"))
    )
    (net (code "32") (name "/~{RESET}") (class "Default")
      (node (ref "1.ISPC") (pin "RST") (pinfunction "P$4_RST") (pintype "bidirectional"))
      (node (ref "1.MCU1") (pin "29") (pinfunction "PC6(~{RESET})_29") (pintype "bidirectional"))
    )
    (net (code "33") (name "AGND") (class "Default")
      (node (ref "2.R1") (pin "1") (pinfunction "1_1") (pintype "passive"))
      (node (ref "2.R3") (pin "1") (pinfunction "1_1") (pintype "passive"))
      (node (ref "2.R5") (pin "1") (pinfunction "1_1") (pintype "passive"))
      (node (ref "2.R7") (pin "1") (pinfunction "1_1") (pintype "passive"))
      (node (ref "2.T0") (pin "2") (pinfunction "P$2_2") (pintype "bidirectional"))
      (node (ref "2.T1") (pin "2") (pinfunction "P$2_2") (pintype "bidirectional"))
      (node (ref "2.T2") (pin "2") (pinfunction "P$2_2") (pintype "bidirectional"))
      (node (ref "2.T3") (pin "2") (pinfunction "P$2_2") (pintype "bidirectional"))
      (node (ref "2.U2") (pin "3") (pinfunction "S_3") (pintype "bidirectional"))
      (node (ref "2.U3") (pin "3") (pinfunction "S_3") (pintype "bidirectional"))
      (node (ref "2.U4") (pin "3") (pinfunction "S_3") (pintype "bidirectional"))
      (node (ref "2.U5") (pin "3") (pinfunction "S_3") (pintype "bidirectional"))
      (node (ref "4.T4") (pin "1") (pinfunction "P$1_1") (pintype "bidirectional"))
      (node (ref "6.T4") (pin "1") (pinfunction "P$1_1") (pintype "bidirectional"))
      (node (ref "6.T4") (pin "2") (pinfunction "P$2_2") (pintype "bidirectional"))
      (node (ref "6.T5") (pin "1") (pinfunction "P$1_1") (pintype "bidirectional"))
      (node (ref "6.T5") (pin "2") (pinfunction "P$2_2") (pintype "bidirectional"))
      (node (ref "6.T6") (pin "1") (pinfunction "P$1_1") (pintype "bidirectional"))
      (node (ref "6.T6") (pin "2") (pinfunction "P$2_2") (pintype "bidirectional"))
    )
    (net (code "34") (name "GND") (class "Default")
      (node (ref "0.C0") (pin "-") (pinfunction "-_-") (pintype "passive"))
      (node (ref "0.C1") (pin "2") (pinfunction "2_2") (pintype "passive"))
      (node (ref "0.C2") (pin "2") (pinfunction "2_2") (pintype "passive"))
      (node (ref "0.C3") (pin "2") (pinfunction "2_2") (pintype "passive"))
      (node (ref "0.C4") (pin "2") (pinfunction "2_2") (pintype "passive"))
      (node (ref "0.CON1") (pin "GND") (pinfunction "GND_GND") (pintype "bidirectional"))
      (node (ref "0.CON1") (pin "SHIELD") (pinfunction "SHIELD_SHIELD") (pintype "bidirectional"))
      (node (ref "0.CON1") (pin "SHIELD@2") (pinfunction "SHIELD_SHIELD@2") (pintype "bidirectional"))
      (node (ref "1.C0") (pin "2") (pinfunction "2_2") (pintype "passive"))
      (node (ref "1.C1") (pin "2") (pinfunction "2_2") (pintype "passive"))
      (node (ref "1.C2") (pin "2") (pinfunction "2_2") (pintype "passive"))
      (node (ref "1.C4") (pin "2") (pinfunction "2_2") (pintype "passive"))
      (node (ref "1.ISPC") (pin "GND") (pinfunction "P$6_GND") (pintype "bidirectional"))
      (node (ref "1.MCU1") (pin "21") (pinfunction "GND_21") (pintype "bidirectional"))
      (node (ref "1.MCU1") (pin "3") (pinfunction "GND_3") (pintype "bidirectional"))
      (node (ref "1.MCU1") (pin "5") (pinfunction "GND_5") (pintype "bidirectional"))
      (node (ref "3.C0") (pin "-") (pinfunction "-_-") (pintype "passive"))
      (node (ref "3.C1") (pin "2") (pinfunction "2_2") (pintype "passive"))
      (node (ref "3.C2") (pin "2") (pinfunction "2_2") (pintype "passive"))
      (node (ref "3.C3") (pin "-") (pinfunction "-_-") (pintype "passive"))
      (node (ref "3.IC0") (pin "1") (pinfunction "GND_1") (pintype "bidirectional"))
      (node (ref "5.R1") (pin "2") (pinfunction "2_2") (pintype "passive"))
      (node (ref "5.R11") (pin "2") (pinfunction "2_2") (pintype "passive"))
      (node (ref "5.R14") (pin "2") (pinfunction "2_2") (pintype "passive"))
      (node (ref "5.R15") (pin "2") (pinfunction "2_2") (pintype "passive"))
      (node (ref "5.R17") (pin "2") (pinfunction "2_2") (pintype "passive"))
      (node (ref "5.R19") (pin "2") (pinfunction "2_2") (pintype "passive"))
      (node (ref "5.R22") (pin "2") (pinfunction "2_2") (pintype "passive"))
      (node (ref "5.R23") (pin "2") (pinfunction "2_2") (pintype "passive"))
      (node (ref "5.R3") (pin "2") (pinfunction "2_2") (pintype "passive"))
      (node (ref "5.R6") (pin "2") (pinfunction "2_2") (pintype "passive"))
      (node (ref "5.R7") (pin "2") (pinfunction "2_2") (pintype "passive"))
      (node (ref "5.R9") (pin "2") (pinfunction "2_2") (pintype "passive"))
      (node (ref "6.T0") (pin "1") (pinfunction "P$1_1") (pintype "bidirectional"))
      (node (ref "6.T0") (pin "2") (pinfunction "P$2_2") (pintype "bidirectional"))
      (node (ref "IC1") (pin "18") (pinfunction "GND_18") (pintype "bidirectional"))
      (node (ref "IC1") (pin "21") (pinfunction "GND_21") (pintype "bidirectional"))
      (node (ref "IC1") (pin "25") (pinfunction "AGND_25") (pintype "bidirectional"))
      (node (ref "IC1") (pin "26") (pinfunction "TEST_26") (pintype "bidirectional"))
      (node (ref "IC1") (pin "7") (pinfunction "GND_7") (pintype "bidirectional"))
      (node (ref "IC2") (pin "2") (pinfunction "CA_2") (pintype "bidirectional"))
      (node (ref "IC2") (pin "4") (pinfunction "CA_4") (pintype "bidirectional"))
      (node (ref "IC2") (pin "6") (pinfunction "CA_6") (pintype "bidirectional"))
      (node (ref "IC2") (pin "8") (pinfunction "CA_8") (pintype "bidirectional"))
    )
    (net (code "35") (name "Net-(1.MCU1-AVCC)") (class "Default")
      (node (ref "1.C2") (pin "1") (pinfunction "1_1") (pintype "passive"))
      (node (ref "1.L1") (pin "2") (pinfunction "2_2") (pintype "passive"))
      (node (ref "1.MCU1") (pin "18") (pinfunction "AVCC_18") (pintype "bidirectional"))
    )
    (net (code "36") (name "Net-(2.T0-P$1)") (class "Default")
      (node (ref "2.T0") (pin "1") (pinfunction "P$1_1") (pintype "bidirectional"))
      (node (ref "2.U2") (pin "2") (pinfunction "D_2") (pintype "bidirectional"))
    )
    (net (code "37") (name "Net-(2.T1-P$1)") (class "Default")
      (node (ref "2.T1") (pin "1") (pinfunction "P$1_1") (pintype "bidirectional"))
      (node (ref "2.U3") (pin "2") (pinfunction "D_2") (pintype "bidirectional"))
    )
    (net (code "38") (name "Net-(2.T2-P$1)") (class "Default")
      (node (ref "2.T2") (pin "1") (pinfunction "P$1_1") (pintype "bidirectional"))
      (node (ref "2.U4") (pin "2") (pinfunction "D_2") (pintype "bidirectional"))
    )
    (net (code "39") (name "Net-(2.T3-P$1)") (class "Default")
      (node (ref "2.T3") (pin "1") (pinfunction "P$1_1") (pintype "bidirectional"))
      (node (ref "2.U5") (pin "2") (pinfunction "D_2") (pintype "bidirectional"))
    )
    (net (code "40") (name "Net-(2.U2-G)") (class "Default")
      (node (ref "2.R1") (pin "2") (pinfunction "2_2") (pintype "passive"))
      (node (ref "2.U2") (pin "1") (pinfunction "G_1") (pintype "bidirectional"))
      (node (ref "IC2") (pin "15") (pinfunction "E_15") (pintype "bidirectional"))
    )
    (net (code "41") (name "Net-(2.U3-G)") (class "Default")
      (node (ref "2.R3") (pin "2") (pinfunction "2_2") (pintype "passive"))
      (node (ref "2.U3") (pin "1") (pinfunction "G_1") (pintype "bidirectional"))
      (node (ref "IC2") (pin "13") (pinfunction "E_13") (pintype "bidirectional"))
    )
    (net (code "42") (name "Net-(2.U4-G)") (class "Default")
      (node (ref "2.R5") (pin "2") (pinfunction "2_2") (pintype "passive"))
      (node (ref "2.U4") (pin "1") (pinfunction "G_1") (pintype "bidirectional"))
      (node (ref "IC2") (pin "11") (pinfunction "E_11") (pintype "bidirectional"))
    )
    (net (code "43") (name "Net-(2.U5-G)") (class "Default")
      (node (ref "2.R7") (pin "2") (pinfunction "2_2") (pintype "passive"))
      (node (ref "2.U5") (pin "1") (pinfunction "G_1") (pintype "bidirectional"))
      (node (ref "IC2") (pin "9") (pinfunction "E_9") (pintype "bidirectional"))
    )
    (net (code "44") (name "Net-(5.T0-P$1)") (class "Default")
      (node (ref "5.R0") (pin "2") (pinfunction "2_2") (pintype "passive"))
      (node (ref "5.T0") (pin "1") (pinfunction "P$1_1") (pintype "bidirectional"))
    )
    (net (code "45") (name "Net-(5.T0-P$2)") (class "Default")
      (node (ref "5.T0") (pin "2") (pinfunction "P$2_2") (pintype "bidirectional"))
      (node (ref "IC3") (pin "2") (pinfunction "CA_2") (pintype "bidirectional"))
    )
    (net (code "46") (name "Net-(5.T1-P$1)") (class "Default")
      (node (ref "5.R2") (pin "2") (pinfunction "2_2") (pintype "passive"))
      (node (ref "5.T1") (pin "1") (pinfunction "P$1_1") (pintype "bidirectional"))
    )
    (net (code "47") (name "Net-(5.T1-P$2)") (class "Default")
      (node (ref "5.T1") (pin "2") (pinfunction "P$2_2") (pintype "bidirectional"))
      (node (ref "IC3") (pin "4") (pinfunction "CA_4") (pintype "bidirectional"))
    )
    (net (code "48") (name "Net-(5.T2-P$1)") (class "Default")
      (node (ref "5.R4") (pin "2") (pinfunction "2_2") (pintype "passive"))
      (node (ref "5.T2") (pin "1") (pinfunction "P$1_1") (pintype "bidirectional"))
    )
    (net (code "49") (name "Net-(5.T2-P$2)") (class "Default")
      (node (ref "5.T2") (pin "2") (pinfunction "P$2_2") (pintype "bidirectional"))
      (node (ref "IC3") (pin "6") (pinfunction "CA_6") (pintype "bidirectional"))
    )
    (net (code "50") (name "Net-(5.T3-P$1)") (class "Default")
      (node (ref "5.R5") (pin "2") (pinfunction "2_2") (pintype "passive"))
      (node (ref "5.T3") (pin "1") (pinfunction "P$1_1") (pintype "bidirectional"))
    )
    (net (code "51") (name "Net-(5.T3-P$2)") (class "Default")
      (node (ref "5.T3") (pin "2") (pinfunction "P$2_2") (pintype "bidirectional"))
      (node (ref "IC3") (pin "8") (pinfunction "CA_8") (pintype "bidirectional"))
    )
    (net (code "52") (name "Net-(5.T4-P$1)") (class "Default")
      (node (ref "5.R8") (pin "2") (pinfunction "2_2") (pintype "passive"))
      (node (ref "5.T4") (pin "1") (pinfunction "P$1_1") (pintype "bidirectional"))
    )
    (net (code "53") (name "Net-(5.T4-P$2)") (class "Default")
      (node (ref "5.T4") (pin "2") (pinfunction "P$2_2") (pintype "bidirectional"))
      (node (ref "IC4") (pin "2") (pinfunction "CA_2") (pintype "bidirectional"))
    )
    (net (code "54") (name "Net-(5.T5-P$1)") (class "Default")
      (node (ref "5.R10") (pin "2") (pinfunction "2_2") (pintype "passive"))
      (node (ref "5.T5") (pin "1") (pinfunction "P$1_1") (pintype "bidirectional"))
    )
    (net (code "55") (name "Net-(5.T5-P$2)") (class "Default")
      (node (ref "5.T5") (pin "2") (pinfunction "P$2_2") (pintype "bidirectional"))
      (node (ref "IC4") (pin "4") (pinfunction "CA_4") (pintype "bidirectional"))
    )
    (net (code "56") (name "Net-(5.T6-P$1)") (class "Default")
      (node (ref "5.R12") (pin "2") (pinfunction "2_2") (pintype "passive"))
      (node (ref "5.T6") (pin "1") (pinfunction "P$1_1") (pintype "bidirectional"))
    )
    (net (code "57") (name "Net-(5.T6-P$2)") (class "Default")
      (node (ref "5.T6") (pin "2") (pinfunction "P$2_2") (pintype "bidirectional"))
      (node (ref "IC4") (pin "6") (pinfunction "CA_6") (pintype "bidirectional"))
    )
    (net (code "58") (name "Net-(5.T7-P$1)") (class "Default")
      (node (ref "5.R13") (pin "2") (pinfunction "2_2") (pintype "passive"))
      (node (ref "5.T7") (pin "1") (pinfunction "P$1_1") (pintype "bidirectional"))
    )
    (net (code "59") (name "Net-(5.T7-P$2)") (class "Default")
      (node (ref "5.T7") (pin "2") (pinfunction "P$2_2") (pintype "bidirectional"))
      (node (ref "IC4") (pin "8") (pinfunction "CA_8") (pintype "bidirectional"))
    )
    (net (code "60") (name "Net-(5.T8-P$1)") (class "Default")
      (node (ref "5.R16") (pin "2") (pinfunction "2_2") (pintype "passive"))
      (node (ref "5.T8") (pin "1") (pinfunction "P$1_1") (pintype "bidirectional"))
    )
    (net (code "61") (name "Net-(5.T8-P$2)") (class "Default")
      (node (ref "5.T8") (pin "2") (pinfunction "P$2_2") (pintype "bidirectional"))
      (node (ref "IC5") (pin "2") (pinfunction "CA_2") (pintype "bidirectional"))
    )
    (net (code "62") (name "Net-(5.T9-P$1)") (class "Default")
      (node (ref "5.R18") (pin "2") (pinfunction "2_2") (pintype "passive"))
      (node (ref "5.T9") (pin "1") (pinfunction "P$1_1") (pintype "bidirectional"))
    )
    (net (code "63") (name "Net-(5.T9-P$2)") (class "Default")
      (node (ref "5.T9") (pin "2") (pinfunction "P$2_2") (pintype "bidirectional"))
      (node (ref "IC5") (pin "4") (pinfunction "CA_4") (pintype "bidirectional"))
    )
    (net (code "64") (name "Net-(5.T10-P$1)") (class "Default")
      (node (ref "5.R20") (pin "2") (pinfunction "2_2") (pintype "passive"))
      (node (ref "5.T10") (pin "1") (pinfunction "P$1_1") (pintype "bidirectional"))
    )
    (net (code "65") (name "Net-(5.T10-P$2)") (class "Default")
      (node (ref "5.T10") (pin "2") (pinfunction "P$2_2") (pintype "bidirectional"))
      (node (ref "IC5") (pin "6") (pinfunction "CA_6") (pintype "bidirectional"))
    )
    (net (code "66") (name "Net-(5.T11-P$1)") (class "Default")
      (node (ref "5.R21") (pin "2") (pinfunction "2_2") (pintype "passive"))
      (node (ref "5.T11") (pin "1") (pinfunction "P$1_1") (pintype "bidirectional"))
    )
    (net (code "67") (name "Net-(5.T11-P$2)") (class "Default")
      (node (ref "5.T11") (pin "2") (pinfunction "P$2_2") (pintype "bidirectional"))
      (node (ref "IC5") (pin "8") (pinfunction "CA_8") (pintype "bidirectional"))
    )
    (net (code "68") (name "Net-(IC1-3V3OUT)") (class "Default")
      (node (ref "0.C4") (pin "1") (pinfunction "1_1") (pintype "passive"))
      (node (ref "IC1") (pin "17") (pinfunction "3V3OUT_17") (pintype "bidirectional"))
    )
    (net (code "69") (name "Net-(IC1-USBDM)") (class "Default")
      (node (ref "0.CON1") (pin "D-") (pinfunction "D-_D-") (pintype "bidirectional"))
      (node (ref "IC1") (pin "16") (pinfunction "USBDM_16") (pintype "bidirectional"))
    )
    (net (code "70") (name "Net-(IC1-USBDP)") (class "Default")
      (node (ref "0.CON1") (pin "D+") (pinfunction "D+_D+") (pintype "bidirectional"))
      (node (ref "IC1") (pin "15") (pinfunction "USBDP_15") (pintype "bidirectional"))
    )
    (net (code "71") (name "Net-(IC2A-AN)") (class "Default")
      (node (ref "2.R0") (pin "1") (pinfunction "1_1") (pintype "passive"))
      (node (ref "IC2") (pin "1") (pinfunction "AN_1") (pintype "bidirectional"))
    )
    (net (code "72") (name "Net-(IC2B-AN)") (class "Default")
      (node (ref "2.R2") (pin "1") (pinfunction "1_1") (pintype "passive"))
      (node (ref "IC2") (pin "3") (pinfunction "AN_3") (pintype "bidirectional"))
    )
    (net (code "73") (name "Net-(IC2C-AN)") (class "Default")
      (node (ref "2.R4") (pin "1") (pinfunction "1_1") (pintype "passive"))
      (node (ref "IC2") (pin "5") (pinfunction "AN_5") (pintype "bidirectional"))
    )
    (net (code "74") (name "Net-(IC2D-AN)") (class "Default")
      (node (ref "2.R6") (pin "1") (pinfunction "1_1") (pintype "passive"))
      (node (ref "IC2") (pin "7") (pinfunction "AN_7") (pintype "bidirectional"))
    )
    (net (code "75") (name "Net-(IC3A-AN)") (class "Default")
      (node (ref "5.R0") (pin "1") (pinfunction "1_1") (pintype "passive"))
      (node (ref "IC3") (pin "1") (pinfunction "AN_1") (pintype "bidirectional"))
    )
    (net (code "76") (name "Net-(IC3B-AN)") (class "Default")
      (node (ref "5.R2") (pin "1") (pinfunction "1_1") (pintype "passive"))
      (node (ref "IC3") (pin "3") (pinfunction "AN_3") (pintype "bidirectional"))
    )
    (net (code "77") (name "Net-(IC3C-AN)") (class "Default")
      (node (ref "5.R4") (pin "1") (pinfunction "1_1") (pintype "passive"))
      (node (ref "IC3") (pin "5") (pinfunction "AN_5") (pintype "bidirectional"))
    )
    (net (code "78") (name "Net-(IC3D-AN)") (class "Default")
      (node (ref "5.R5") (pin "1") (pinfunction "1_1") (pintype "passive"))
      (node (ref "IC3") (pin "7") (pinfunction "AN_7") (pintype "bidirectional"))
    )
    (net (code "79") (name "Net-(IC4A-AN)") (class "Default")
      (node (ref "5.R8") (pin "1") (pinfunction "1_1") (pintype "passive"))
      (node (ref "IC4") (pin "1") (pinfunction "AN_1") (pintype "bidirectional"))
    )
    (net (code "80") (name "Net-(IC4B-AN)") (class "Default")
      (node (ref "5.R10") (pin "1") (pinfunction "1_1") (pintype "passive"))
      (node (ref "IC4") (pin "3") (pinfunction "AN_3") (pintype "bidirectional"))
    )
    (net (code "81") (name "Net-(IC4C-AN)") (class "Default")
      (node (ref "5.R12") (pin "1") (pinfunction "1_1") (pintype "passive"))
      (node (ref "IC4") (pin "5") (pinfunction "AN_5") (pintype "bidirectional"))
    )
    (net (code "82") (name "Net-(IC4D-AN)") (class "Default")
      (node (ref "5.R13") (pin "1") (pinfunction "1_1") (pintype "passive"))
      (node (ref "IC4") (pin "7") (pinfunction "AN_7") (pintype "bidirectional"))
    )
    (net (code "83") (name "Net-(IC5A-AN)") (class "Default")
      (node (ref "5.R16") (pin "1") (pinfunction "1_1") (pintype "passive"))
      (node (ref "IC5") (pin "1") (pinfunction "AN_1") (pintype "bidirectional"))
    )
    (net (code "84") (name "Net-(IC5B-AN)") (class "Default")
      (node (ref "5.R18") (pin "1") (pinfunction "1_1") (pintype "passive"))
      (node (ref "IC5") (pin "3") (pinfunction "AN_3") (pintype "bidirectional"))
    )
    (net (code "85") (name "Net-(IC5C-AN)") (class "Default")
      (node (ref "5.R20") (pin "1") (pinfunction "1_1") (pintype "passive"))
      (node (ref "IC5") (pin "5") (pinfunction "AN_5") (pintype "bidirectional"))
    )
    (net (code "86") (name "Net-(IC5D-AN)") (class "Default")
      (node (ref "5.R21") (pin "1") (pinfunction "1_1") (pintype "passive"))
      (node (ref "IC5") (pin "7") (pinfunction "AN_7") (pintype "bidirectional"))
    )
    (net (code "87") (name "unconnected-(IC1-#RESET-Pad19)") (class "Default")
      (node (ref "IC1") (pin "19") (pinfunction "#RESET_19") (pintype "bidirectional"))
    )
    (net (code "88") (name "unconnected-(IC1-CBUS0-Pad23)") (class "Default")
      (node (ref "IC1") (pin "23") (pinfunction "CBUS0_23") (pintype "bidirectional"))
    )
    (net (code "89") (name "unconnected-(IC1-CBUS1-Pad22)") (class "Default")
      (node (ref "IC1") (pin "22") (pinfunction "CBUS1_22") (pintype "bidirectional"))
    )
    (net (code "90") (name "unconnected-(IC1-CBUS2-Pad13)") (class "Default")
      (node (ref "IC1") (pin "13") (pinfunction "CBUS2_13") (pintype "bidirectional"))
    )
    (net (code "91") (name "unconnected-(IC1-CBUS3-Pad14)") (class "Default")
      (node (ref "IC1") (pin "14") (pinfunction "CBUS3_14") (pintype "bidirectional"))
    )
    (net (code "92") (name "unconnected-(IC1-CBUS4-Pad12)") (class "Default")
      (node (ref "IC1") (pin "12") (pinfunction "CBUS4_12") (pintype "bidirectional"))
    )
    (net (code "93") (name "unconnected-(IC1-CTS#-Pad11)") (class "Default")
      (node (ref "IC1") (pin "11") (pinfunction "CTS#_11") (pintype "bidirectional"))
    )
    (net (code "94") (name "unconnected-(IC1-DCD#-Pad10)") (class "Default")
      (node (ref "IC1") (pin "10") (pinfunction "DCD#_10") (pintype "bidirectional"))
    )
    (net (code "95") (name "unconnected-(IC1-DSR#-Pad9)") (class "Default")
      (node (ref "IC1") (pin "9") (pinfunction "DSR#_9") (pintype "bidirectional"))
    )
    (net (code "96") (name "unconnected-(IC1-DTR#-Pad2)") (class "Default")
      (node (ref "IC1") (pin "2") (pinfunction "DTR#_2") (pintype "bidirectional"))
    )
    (net (code "97") (name "unconnected-(IC1-OSCI-Pad27)") (class "Default")
      (node (ref "IC1") (pin "27") (pinfunction "OSCI_27") (pintype "bidirectional"))
    )
    (net (code "98") (name "unconnected-(IC1-OSCO-Pad28)") (class "Default")
      (node (ref "IC1") (pin "28") (pinfunction "OSCO_28") (pintype "bidirectional"))
    )
    (net (code "99") (name "unconnected-(IC1-RI#-Pad6)") (class "Default")
      (node (ref "IC1") (pin "6") (pinfunction "RI#_6") (pintype "bidirectional"))
    )
    (net (code "100") (name "unconnected-(IC1-RTS#-Pad3)") (class "Default")
      (node (ref "IC1") (pin "3") (pinfunction "RTS#_3") (pintype "bidirectional"))
    )
  )
)
